# MINI_SAM_D51_011.net
KiCad netlist of a schematic drawn in EAGLE
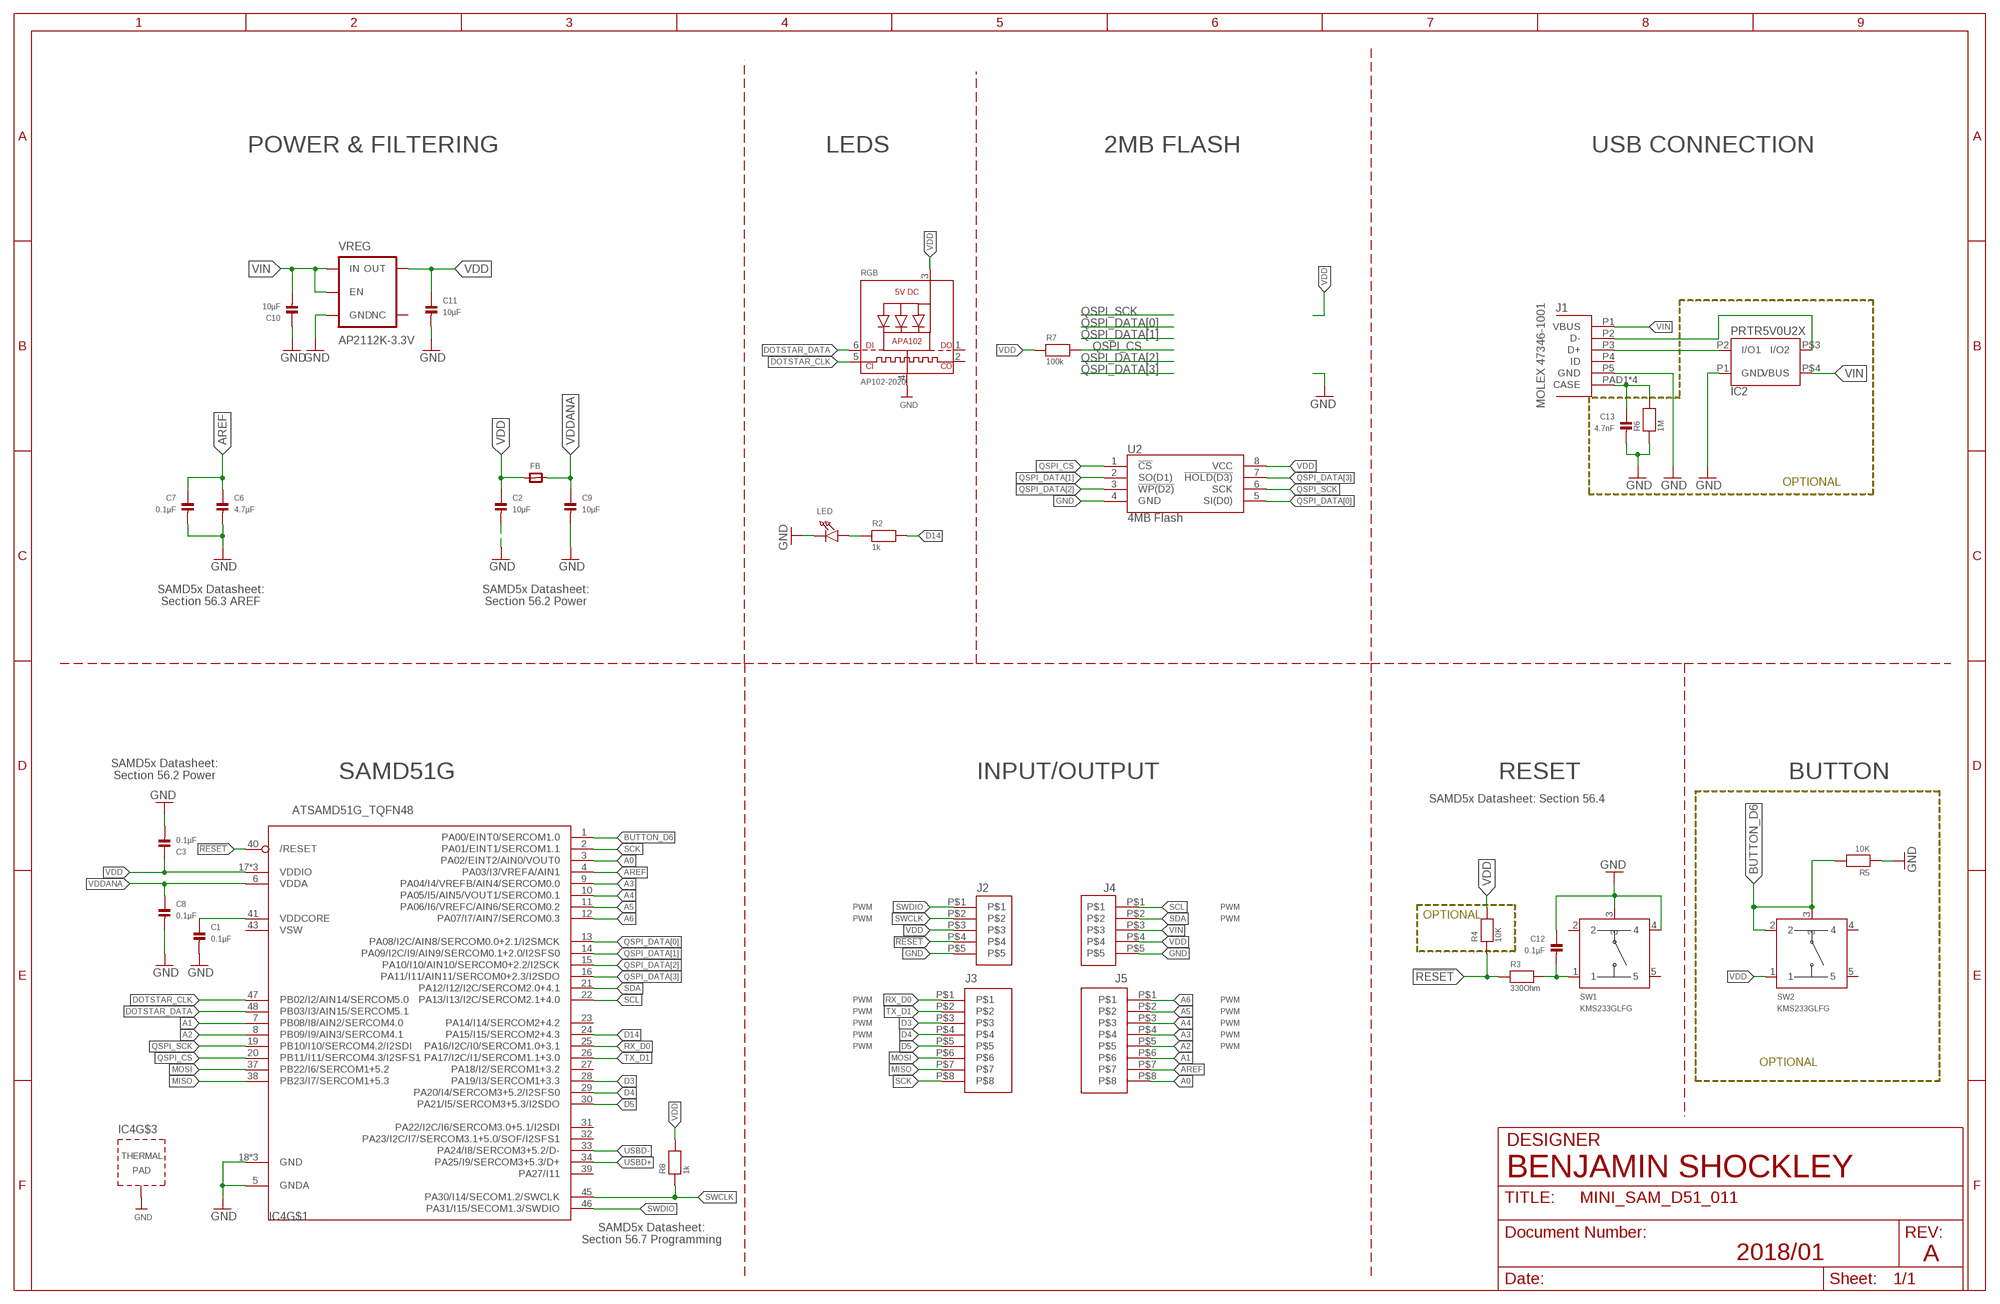
[diagram p0: schematic, sheet 1]

(export (version "E")
  (design (tool "Eeschema 10.0.6"))
  (components
    (comp (ref "C1")
      (value "0.1µF")
      (footprint "eagle-import:_0603MP")
      (libsource (lib "eagle-import") (part "CAP_CERAMIC_0603MP"))
    )
    (comp (ref "C2")
      (value "10µF")
      (footprint "eagle-import:_0603MP")
      (libsource (lib "eagle-import") (part "CAP_CERAMIC_0603MP"))
    )
    (comp (ref "C3")
      (value "0.1µF")
      (footprint "eagle-import:_0603MP")
      (libsource (lib "eagle-import") (part "CAP_CERAMIC_0603MP"))
    )
    (comp (ref "C6")
      (value "4.7µF")
      (footprint "eagle-import:_0603MP")
      (libsource (lib "eagle-import") (part "CAP_CERAMIC_0603MP"))
    )
    (comp (ref "C7")
      (value "0.1µF")
      (footprint "eagle-import:_0603MP")
      (libsource (lib "eagle-import") (part "CAP_CERAMIC_0603MP"))
    )
    (comp (ref "C8")
      (value "0.1µF")
      (footprint "eagle-import:_0603MP")
      (libsource (lib "eagle-import") (part "CAP_CERAMIC_0603MP"))
    )
    (comp (ref "C9")
      (value "10µF")
      (footprint "eagle-import:_0603MP")
      (libsource (lib "eagle-import") (part "CAP_CERAMIC_0603MP"))
    )
    (comp (ref "C10")
      (value "10µF")
      (footprint "eagle-import:_0603MP")
      (libsource (lib "eagle-import") (part "CAP_CERAMIC_0603MP"))
    )
    (comp (ref "C11")
      (value "10µF")
      (footprint "eagle-import:_0603MP")
      (libsource (lib "eagle-import") (part "CAP_CERAMIC_0603MP"))
    )
    (comp (ref "C12")
      (value "0.1µF")
      (footprint "eagle-import:_0603MP")
      (libsource (lib "eagle-import") (part "CAP_CERAMIC_0603MP"))
    )
    (comp (ref "C13")
      (value "4.7nF")
      (footprint "eagle-import:_0603MP")
      (libsource (lib "eagle-import") (part "CAP_CERAMIC_0603MP"))
    )
    (comp (ref "FB")
      (value "FERRITE_0603MP")
      (footprint "eagle-import:_0603MP")
      (libsource (lib "eagle-import") (part "FERRITE_0603MP"))
    )
    (comp (ref "IC2")
      (value "PRTR5V0U2X")
      (footprint "eagle-import:SOT143B_REFLOW")
      (libsource (lib "eagle-import") (part "PRTR5V0U2X"))
    )
    (comp (ref "IC4")
      (value "ATSAMD51G_TQFN48")
      (footprint "eagle-import:TQFN48_7MM")
      (libsource (lib "eagle-import") (part "ATSAMD51G_TQFN48"))
    )
    (comp (ref "J1")
      (value "MOLEX_47346-100147346")
      (footprint "eagle-import:MOLEX_47346-1001")
      (libsource (lib "eagle-import") (part "MOLEX_47346-100147346"))
    )
    (comp (ref "J2")
      (value "1X5_HEADER_1.27MM")
      (footprint "eagle-import:1X5_HEADER_1.27MM")
      (libsource (lib "eagle-import") (part "1X5_HEADER_1.27MM"))
    )
    (comp (ref "J3")
      (value "1X8_HEADER_1.27MM")
      (footprint "eagle-import:1X8_HEADER_1.27MM")
      (libsource (lib "eagle-import") (part "1X8_HEADER_1.27MM"))
    )
    (comp (ref "J4")
      (value "1X5_HEADER_1.27MM")
      (footprint "eagle-import:1X5_HEADER_1.27MM")
      (libsource (lib "eagle-import") (part "1X5_HEADER_1.27MM"))
    )
    (comp (ref "J5")
      (value "1X8_HEADER_1.27MM")
      (footprint "eagle-import:1X8_HEADER_1.27MM")
      (libsource (lib "eagle-import") (part "1X8_HEADER_1.27MM"))
    )
    (comp (ref "LED")
      (value "LED0805_NOOUTLINE")
      (footprint "eagle-import:CHIPLED_0805_NOOUTLINE")
      (libsource (lib "eagle-import") (part "LED0805_NOOUTLINE"))
    )
    (comp (ref "R2")
      (value "1k")
      (footprint "eagle-import:_0603MP")
      (libsource (lib "eagle-import") (part "RESISTOR_0603MP"))
    )
    (comp (ref "R3")
      (value "330Ohm")
      (footprint "eagle-import:_0603MP")
      (libsource (lib "eagle-import") (part "RESISTOR_0603MP"))
    )
    (comp (ref "R4")
      (value "10K")
      (footprint "eagle-import:_0603MP")
      (libsource (lib "eagle-import") (part "RESISTOR_0603MP"))
    )
    (comp (ref "R5")
      (value "10K")
      (footprint "eagle-import:_0603MP")
      (libsource (lib "eagle-import") (part "RESISTOR_0603MP"))
    )
    (comp (ref "R6")
      (value "1M")
      (footprint "eagle-import:_0603MP")
      (libsource (lib "eagle-import") (part "RESISTOR_0603MP"))
    )
    (comp (ref "R7")
      (value "100k")
      (footprint "eagle-import:_0603MP")
      (libsource (lib "eagle-import") (part "RESISTOR_0603MP"))
    )
    (comp (ref "R8")
      (value "1k")
      (footprint "eagle-import:_0603MP")
      (libsource (lib "eagle-import") (part "RESISTOR_0603MP"))
    )
    (comp (ref "RGB")
      (value "AP102-2020")
      (footprint "eagle-import:APA102_2020")
      (libsource (lib "eagle-import") (part "APA1022020"))
    )
    (comp (ref "SW1")
      (value "KMS233GLFG")
      (footprint "eagle-import:KMS_SWITCH")
      (libsource (lib "eagle-import") (part "KMS_SWITCHKMS"))
    )
    (comp (ref "SW2")
      (value "KMS233GLFG")
      (footprint "eagle-import:KMS_SWITCH")
      (libsource (lib "eagle-import") (part "KMS_SWITCHKMS"))
    )
    (comp (ref "U2")
      (value "4MB Flash")
      (footprint "eagle-import:SO08")
      (libsource (lib "eagle-import") (part "AT25SF041"))
    )
    (comp (ref "VREG")
      (value "AP2112K-3.3V")
      (footprint "eagle-import:SOT23-5")
      (libsource (lib "eagle-import") (part "V_REG_AP2112K-3.3V"))
    )
  )
  (nets
    (net (code "1") (name "/VSW") (class "Default")
      (node (ref "IC4") (pin "43") (pinfunction "VSW_43") (pintype "power_in"))
    )
    (net (code "2") (name "/~{RESET}") (class "Default")
      (node (ref "IC4") (pin "40") (pinfunction "/RESET_40") (pintype "bidirectional"))
      (node (ref "J2") (pin "P$4") (pinfunction "P$4_P$4") (pintype "bidirectional"))
      (node (ref "R3") (pin "1") (pinfunction "1_1") (pintype "passive"))
      (node (ref "R4") (pin "1") (pinfunction "1_1") (pintype "passive"))
    )
    (net (code "3") (name "A0") (class "Default")
      (node (ref "IC4") (pin "3") (pinfunction "PA02/EINT2/AIN0/VOUT0_3") (pintype "bidirectional"))
      (node (ref "J5") (pin "P$8") (pinfunction "P$8_P$8") (pintype "bidirectional"))
    )
    (net (code "4") (name "A1") (class "Default")
      (node (ref "IC4") (pin "7") (pinfunction "PB08/I8/AIN2/SERCOM4.0_7") (pintype "bidirectional"))
      (node (ref "J5") (pin "P$6") (pinfunction "P$6_P$6") (pintype "bidirectional"))
    )
    (net (code "5") (name "A2") (class "Default")
      (node (ref "IC4") (pin "8") (pinfunction "PB09/I9/AIN3/SERCOM4.1_8") (pintype "bidirectional"))
      (node (ref "J5") (pin "P$5") (pinfunction "P$5_P$5") (pintype "bidirectional"))
    )
    (net (code "6") (name "A3") (class "Default")
      (node (ref "IC4") (pin "9") (pinfunction "PA04/I4/VREFB/AIN4/SERCOM0.0_9") (pintype "bidirectional"))
      (node (ref "J5") (pin "P$4") (pinfunction "P$4_P$4") (pintype "bidirectional"))
    )
    (net (code "7") (name "A4") (class "Default")
      (node (ref "IC4") (pin "10") (pinfunction "PA05/I5/AIN5/VOUT1/SERCOM0.1_10") (pintype "bidirectional"))
      (node (ref "J5") (pin "P$3") (pinfunction "P$3_P$3") (pintype "bidirectional"))
    )
    (net (code "8") (name "A5") (class "Default")
      (node (ref "IC4") (pin "11") (pinfunction "PA06/I6/VREFC/AIN6/SERCOM0.2_11") (pintype "bidirectional"))
      (node (ref "J5") (pin "P$2") (pinfunction "P$2_P$2") (pintype "bidirectional"))
    )
    (net (code "9") (name "A6") (class "Default")
      (node (ref "IC4") (pin "12") (pinfunction "PA07/I7/AIN7/SERCOM0.3_12") (pintype "bidirectional"))
      (node (ref "J5") (pin "P$1") (pinfunction "P$1_P$1") (pintype "bidirectional"))
    )
    (net (code "10") (name "AREF") (class "Default")
      (node (ref "C6") (pin "1") (pinfunction "P$1_1") (pintype "passive"))
      (node (ref "C7") (pin "1") (pinfunction "P$1_1") (pintype "passive"))
      (node (ref "IC4") (pin "4") (pinfunction "PA03/I3/VREFA/AIN1_4") (pintype "bidirectional"))
      (node (ref "J5") (pin "P$7") (pinfunction "P$7_P$7") (pintype "bidirectional"))
    )
    (net (code "11") (name "BUTTON_D6") (class "Default")
      (node (ref "IC4") (pin "1") (pinfunction "PA00/EINT0/SERCOM1.0_1") (pintype "bidirectional"))
      (node (ref "R5") (pin "2") (pinfunction "2_2") (pintype "passive"))
      (node (ref "SW2") (pin "2") (pinfunction "2_2") (pintype "bidirectional"))
      (node (ref "SW2") (pin "3") (pinfunction "3_3") (pintype "bidirectional"))
    )
    (net (code "12") (name "D3") (class "Default")
      (node (ref "IC4") (pin "28") (pinfunction "PA19/I3/SERCOM1+3.3_28") (pintype "bidirectional"))
      (node (ref "J3") (pin "P$3") (pinfunction "P$3_P$3") (pintype "bidirectional"))
    )
    (net (code "13") (name "D4") (class "Default")
      (node (ref "IC4") (pin "29") (pinfunction "PA20/I4/SERCOM3+5.2/I2SFS0_29") (pintype "bidirectional"))
      (node (ref "J3") (pin "P$4") (pinfunction "P$4_P$4") (pintype "bidirectional"))
    )
    (net (code "14") (name "D5") (class "Default")
      (node (ref "IC4") (pin "30") (pinfunction "PA21/I5/SERCOM3+5.3/I2SDO_30") (pintype "bidirectional"))
      (node (ref "J3") (pin "P$5") (pinfunction "P$5_P$5") (pintype "bidirectional"))
    )
    (net (code "15") (name "D14") (class "Default")
      (node (ref "IC4") (pin "24") (pinfunction "PA15/I15/SERCOM2+4.3_24") (pintype "bidirectional"))
      (node (ref "R2") (pin "2") (pinfunction "2_2") (pintype "passive"))
    )
    (net (code "16") (name "DOTSTAR_CLK") (class "Default")
      (node (ref "IC4") (pin "47") (pinfunction "PB02/I2/AIN14/SERCOM5.0_47") (pintype "bidirectional"))
      (node (ref "RGB") (pin "5") (pinfunction "CKI_5") (pintype "input"))
    )
    (net (code "17") (name "DOTSTAR_DATA") (class "Default")
      (node (ref "IC4") (pin "48") (pinfunction "PB03/I3/AIN15/SERCOM5.1_48") (pintype "bidirectional"))
      (node (ref "RGB") (pin "6") (pinfunction "DI_6") (pintype "input"))
    )
    (net (code "18") (name "GND") (class "Default")
      (node (ref "C1") (pin "2") (pinfunction "P$2_2") (pintype "passive"))
      (node (ref "C10") (pin "1") (pinfunction "P$1_1") (pintype "passive"))
      (node (ref "C11") (pin "2") (pinfunction "P$2_2") (pintype "passive"))
      (node (ref "C12") (pin "1") (pinfunction "P$1_1") (pintype "passive"))
      (node (ref "C13") (pin "2") (pinfunction "P$2_2") (pintype "passive"))
      (node (ref "C2") (pin "2") (pinfunction "P$2_2") (pintype "passive"))
      (node (ref "C3") (pin "2") (pinfunction "P$2_2") (pintype "passive"))
      (node (ref "C6") (pin "2") (pinfunction "P$2_2") (pintype "passive"))
      (node (ref "C7") (pin "2") (pinfunction "P$2_2") (pintype "passive"))
      (node (ref "C8") (pin "2") (pinfunction "P$2_2") (pintype "passive"))
      (node (ref "C9") (pin "2") (pinfunction "P$2_2") (pintype "passive"))
      (node (ref "IC2") (pin "P1") (pinfunction "GND_P1") (pintype "bidirectional"))
      (node (ref "IC4") (pin "18") (pinfunction "GND_18") (pintype "power_in"))
      (node (ref "IC4") (pin "35") (pinfunction "GND_35") (pintype "power_in"))
      (node (ref "IC4") (pin "42") (pinfunction "GND_42") (pintype "power_in"))
      (node (ref "IC4") (pin "5") (pinfunction "GNDA_5") (pintype "power_in"))
      (node (ref "IC4") (pin "THERMAL") (pinfunction "TP_THERMAL") (pintype "power_in"))
      (node (ref "J1") (pin "P5") (pinfunction "GND_P5") (pintype "power_in"))
      (node (ref "J2") (pin "P$5") (pinfunction "P$5_P$5") (pintype "bidirectional"))
      (node (ref "J4") (pin "P$5") (pinfunction "P$5_P$5") (pintype "bidirectional"))
      (node (ref "LED") (pin "C") (pinfunction "C_C") (pintype "passive"))
      (node (ref "R5") (pin "1") (pinfunction "1_1") (pintype "passive"))
      (node (ref "R6") (pin "1") (pinfunction "1_1") (pintype "passive"))
      (node (ref "RGB") (pin "4") (pinfunction "GND_4") (pintype "power_in"))
      (node (ref "SW1") (pin "3") (pinfunction "3_3") (pintype "bidirectional"))
      (node (ref "SW1") (pin "4") (pinfunction "4_4") (pintype "bidirectional"))
      (node (ref "U2") (pin "4") (pinfunction "GND_4") (pintype "bidirectional"))
      (node (ref "VREG") (pin "2") (pinfunction "GND_2") (pintype "input"))
    )
    (net (code "19") (name "MISO") (class "Default")
      (node (ref "IC4") (pin "38") (pinfunction "PB23/I7/SERCOM1+5.3_38") (pintype "bidirectional"))
      (node (ref "J3") (pin "P$7") (pinfunction "P$7_P$7") (pintype "bidirectional"))
    )
    (net (code "20") (name "MOSI") (class "Default")
      (node (ref "IC4") (pin "37") (pinfunction "PB22/I6/SERCOM1+5.2_37") (pintype "bidirectional"))
      (node (ref "J3") (pin "P$6") (pinfunction "P$6_P$6") (pintype "bidirectional"))
    )
    (net (code "21") (name "Net-(C1-P$1)") (class "Default")
      (node (ref "C1") (pin "1") (pinfunction "P$1_1") (pintype "passive"))
      (node (ref "IC4") (pin "41") (pinfunction "VDDCORE_41") (pintype "power_in"))
    )
    (net (code "22") (name "Net-(C12-P$2)") (class "Default")
      (node (ref "C12") (pin "2") (pinfunction "P$2_2") (pintype "passive"))
      (node (ref "R3") (pin "2") (pinfunction "2_2") (pintype "passive"))
      (node (ref "SW1") (pin "1") (pinfunction "1_1") (pintype "bidirectional"))
    )
    (net (code "23") (name "Net-(C13-P$1)") (class "Default")
      (node (ref "C13") (pin "1") (pinfunction "P$1_1") (pintype "passive"))
      (node (ref "J1") (pin "PAD1") (pinfunction "CASE_PAD1") (pintype "bidirectional"))
      (node (ref "J1") (pin "PAD2") (pinfunction "CASE_PAD2") (pintype "bidirectional"))
      (node (ref "J1") (pin "PAD3") (pinfunction "CASE_PAD3") (pintype "bidirectional"))
      (node (ref "J1") (pin "PAD4") (pinfunction "CASE_PAD4") (pintype "bidirectional"))
      (node (ref "R6") (pin "2") (pinfunction "2_2") (pintype "passive"))
    )
    (net (code "24") (name "Net-(LED-PadA)") (class "Default")
      (node (ref "LED") (pin "A") (pinfunction "A_A") (pintype "passive"))
      (node (ref "R2") (pin "1") (pinfunction "1_1") (pintype "passive"))
    )
    (net (code "25") (name "QSPI_CS") (class "Default")
      (node (ref "IC4") (pin "20") (pinfunction "PB11/I11/SERCOM4.3/I2SFS1_20") (pintype "bidirectional"))
      (node (ref "R7") (pin "2") (pinfunction "2_2") (pintype "passive"))
      (node (ref "U2") (pin "1") (pinfunction "~{CS}_1") (pintype "bidirectional"))
    )
    (net (code "26") (name "QSPI_DATA[0]") (class "Default")
      (node (ref "IC4") (pin "13") (pinfunction "PA08/I2C/AIN8/SERCOM0.0+2.1/I2SMCK_13") (pintype "bidirectional"))
      (node (ref "U2") (pin "5") (pinfunction "SI(D0)_5") (pintype "bidirectional"))
    )
    (net (code "27") (name "QSPI_DATA[1]") (class "Default")
      (node (ref "IC4") (pin "14") (pinfunction "PA09/I2C/I9/AIN9/SERCOM0.1+2.0/I2SFS0_14") (pintype "bidirectional"))
      (node (ref "U2") (pin "2") (pinfunction "SO(D1)_2") (pintype "bidirectional"))
    )
    (net (code "28") (name "QSPI_DATA[2]") (class "Default")
      (node (ref "IC4") (pin "15") (pinfunction "PA10/I10/AIN10/SERCOM0+2.2/I2SCK_15") (pintype "bidirectional"))
      (node (ref "U2") (pin "3") (pinfunction "~{WP(D2})_3") (pintype "bidirectional"))
    )
    (net (code "29") (name "QSPI_DATA[3]") (class "Default")
      (node (ref "IC4") (pin "16") (pinfunction "PA11/I11/AIN11/SERCOM0+2.3/I2SDO_16") (pintype "bidirectional"))
      (node (ref "U2") (pin "7") (pinfunction "~{HOLD(D3})_7") (pintype "bidirectional"))
    )
    (net (code "30") (name "QSPI_SCK") (class "Default")
      (node (ref "IC4") (pin "19") (pinfunction "PB10/I10/SERCOM4.2/I2SDI_19") (pintype "bidirectional"))
      (node (ref "U2") (pin "6") (pinfunction "SCK_6") (pintype "bidirectional"))
    )
    (net (code "31") (name "RX_D0") (class "Default")
      (node (ref "IC4") (pin "25") (pinfunction "PA16/I2C/I0/SERCOM1.0+3.1_25") (pintype "bidirectional"))
      (node (ref "J3") (pin "P$1") (pinfunction "P$1_P$1") (pintype "bidirectional"))
    )
    (net (code "32") (name "SCK") (class "Default")
      (node (ref "IC4") (pin "2") (pinfunction "PA01/EINT1/SERCOM1.1_2") (pintype "bidirectional"))
      (node (ref "J3") (pin "P$8") (pinfunction "P$8_P$8") (pintype "bidirectional"))
    )
    (net (code "33") (name "SCL") (class "Default")
      (node (ref "IC4") (pin "22") (pinfunction "PA13/I13/I2C/SERCOM2.1+4.0_22") (pintype "bidirectional"))
      (node (ref "J4") (pin "P$1") (pinfunction "P$1_P$1") (pintype "bidirectional"))
    )
    (net (code "34") (name "SDA") (class "Default")
      (node (ref "IC4") (pin "21") (pinfunction "PA12/I12/I2C/SERCOM2.0+4.1_21") (pintype "bidirectional"))
      (node (ref "J4") (pin "P$2") (pinfunction "P$2_P$2") (pintype "bidirectional"))
    )
    (net (code "35") (name "SWCLK") (class "Default")
      (node (ref "IC4") (pin "45") (pinfunction "PA30/I14/SECOM1.2/SWCLK_45") (pintype "bidirectional"))
      (node (ref "J2") (pin "P$2") (pinfunction "P$2_P$2") (pintype "bidirectional"))
      (node (ref "R8") (pin "1") (pinfunction "1_1") (pintype "passive"))
    )
    (net (code "36") (name "SWDIO") (class "Default")
      (node (ref "IC4") (pin "46") (pinfunction "PA31/I15/SECOM1.3/SWDIO_46") (pintype "bidirectional"))
      (node (ref "J2") (pin "P$1") (pinfunction "P$1_P$1") (pintype "bidirectional"))
    )
    (net (code "37") (name "TX_D1") (class "Default")
      (node (ref "IC4") (pin "26") (pinfunction "PA17/I2C/I1/SERCOM1.1+3.0_26") (pintype "bidirectional"))
      (node (ref "J3") (pin "P$2") (pinfunction "P$2_P$2") (pintype "bidirectional"))
    )
    (net (code "38") (name "USBD+") (class "Default")
      (node (ref "IC2") (pin "P2") (pinfunction "I/O1_P2") (pintype "bidirectional"))
      (node (ref "IC4") (pin "34") (pinfunction "PA25/I9/SERCOM3+5.3/D+_34") (pintype "bidirectional"))
      (node (ref "J1") (pin "P3") (pinfunction "D+_P3") (pintype "bidirectional"))
    )
    (net (code "39") (name "USBD-") (class "Default")
      (node (ref "IC2") (pin "P$3") (pinfunction "I/O2_P$3") (pintype "bidirectional"))
      (node (ref "IC4") (pin "33") (pinfunction "PA24/I8/SERCOM3+5.2/D-_33") (pintype "bidirectional"))
      (node (ref "J1") (pin "P2") (pinfunction "D-_P2") (pintype "bidirectional"))
    )
    (net (code "40") (name "VDD") (class "Default")
      (node (ref "C11") (pin "1") (pinfunction "P$1_1") (pintype "passive"))
      (node (ref "C2") (pin "1") (pinfunction "P$1_1") (pintype "passive"))
      (node (ref "C3") (pin "1") (pinfunction "P$1_1") (pintype "passive"))
      (node (ref "FB") (pin "1") (pinfunction "P$1_1") (pintype "passive"))
      (node (ref "IC4") (pin "17") (pinfunction "VDDIO_17") (pintype "power_in"))
      (node (ref "IC4") (pin "36") (pinfunction "VDDIO_36") (pintype "power_in"))
      (node (ref "IC4") (pin "44") (pinfunction "VDDIO_44") (pintype "power_in"))
      (node (ref "J2") (pin "P$3") (pinfunction "P$3_P$3") (pintype "bidirectional"))
      (node (ref "J4") (pin "P$4") (pinfunction "P$4_P$4") (pintype "bidirectional"))
      (node (ref "R4") (pin "2") (pinfunction "2_2") (pintype "passive"))
      (node (ref "R7") (pin "1") (pinfunction "1_1") (pintype "passive"))
      (node (ref "R8") (pin "2") (pinfunction "2_2") (pintype "passive"))
      (node (ref "RGB") (pin "3") (pinfunction "VDD_3") (pintype "power_in"))
      (node (ref "SW2") (pin "1") (pinfunction "1_1") (pintype "bidirectional"))
      (node (ref "U2") (pin "8") (pinfunction "VCC_8") (pintype "bidirectional"))
      (node (ref "VREG") (pin "5") (pinfunction "OUT_5") (pintype "passive"))
    )
    (net (code "41") (name "VDDANA") (class "Default")
      (node (ref "C8") (pin "1") (pinfunction "P$1_1") (pintype "passive"))
      (node (ref "C9") (pin "1") (pinfunction "P$1_1") (pintype "passive"))
      (node (ref "FB") (pin "2") (pinfunction "P$2_2") (pintype "passive"))
      (node (ref "IC4") (pin "6") (pinfunction "VDDA_6") (pintype "power_in"))
    )
    (net (code "42") (name "VIN") (class "Default")
      (node (ref "C10") (pin "2") (pinfunction "P$2_2") (pintype "passive"))
      (node (ref "IC2") (pin "P$4") (pinfunction "VBUS_P$4") (pintype "bidirectional"))
      (node (ref "J1") (pin "P1") (pinfunction "VBUS_P1") (pintype "power_in"))
      (node (ref "J4") (pin "P$3") (pinfunction "P$3_P$3") (pintype "bidirectional"))
      (node (ref "VREG") (pin "1") (pinfunction "IN_1") (pintype "input"))
      (node (ref "VREG") (pin "3") (pinfunction "EN_3") (pintype "input"))
    )
    (net (code "43") (name "unconnected-(IC4A-PA14{slash}I14{slash}SERCOM2+4.2-Pad23)") (class "Default")
      (node (ref "IC4") (pin "23") (pinfunction "PA14/I14/SERCOM2+4.2_23") (pintype "bidirectional"))
    )
    (net (code "44") (name "unconnected-(IC4A-PA18{slash}I2{slash}SERCOM1+3.2-Pad27)") (class "Default")
      (node (ref "IC4") (pin "27") (pinfunction "PA18/I2/SERCOM1+3.2_27") (pintype "bidirectional"))
    )
    (net (code "45") (name "unconnected-(IC4A-PA22{slash}I2C{slash}I6{slash}SERCOM3.0+5.1{slash}I2SDI-Pad31)") (class "Default")
      (node (ref "IC4") (pin "31") (pinfunction "PA22/I2C/I6/SERCOM3.0+5.1/I2SDI_31") (pintype "bidirectional"))
    )
    (net (code "46") (name "unconnected-(IC4A-PA23{slash}I2C{slash}I7{slash}SERCOM3.1+5.0{slash}SOF{slash}I2SFS1-Pad32)") (class "Default")
      (node (ref "IC4") (pin "32") (pinfunction "PA23/I2C/I7/SERCOM3.1+5.0/SOF/I2SFS1_32") (pintype "bidirectional"))
    )
    (net (code "47") (name "unconnected-(IC4A-PA27{slash}I11-Pad39)") (class "Default")
      (node (ref "IC4") (pin "39") (pinfunction "PA27/I11_39") (pintype "bidirectional"))
    )
    (net (code "48") (name "unconnected-(J1-ID-PadP4)") (class "Default")
      (node (ref "J1") (pin "P4") (pinfunction "ID_P4") (pintype "bidirectional"))
    )
    (net (code "49") (name "unconnected-(RGB-CKO-Pad2)") (class "Default")
      (node (ref "RGB") (pin "2") (pinfunction "CKO_2") (pintype "output"))
    )
    (net (code "50") (name "unconnected-(RGB-DO-Pad1)") (class "Default")
      (node (ref "RGB") (pin "1") (pinfunction "DO_1") (pintype "output"))
    )
    (net (code "51") (name "unconnected-(SW1-Pad2)") (class "Default")
      (node (ref "SW1") (pin "2") (pinfunction "2_2") (pintype "bidirectional"))
    )
    (net (code "52") (name "unconnected-(SW1-Pad5)") (class "Default")
      (node (ref "SW1") (pin "5") (pinfunction "5_5") (pintype "bidirectional"))
    )
    (net (code "53") (name "unconnected-(SW2-Pad4)") (class "Default")
      (node (ref "SW2") (pin "4") (pinfunction "4_4") (pintype "bidirectional"))
    )
    (net (code "54") (name "unconnected-(SW2-Pad5)") (class "Default")
      (node (ref "SW2") (pin "5") (pinfunction "5_5") (pintype "bidirectional"))
    )
    (net (code "55") (name "unconnected-(VREG-NC-Pad4)") (class "Default")
      (node (ref "VREG") (pin "4") (pinfunction "NC_4") (pintype "input"))
    )
  )
)
